# Power.net
KiCad netlist of a schematic drawn in Altium Designer
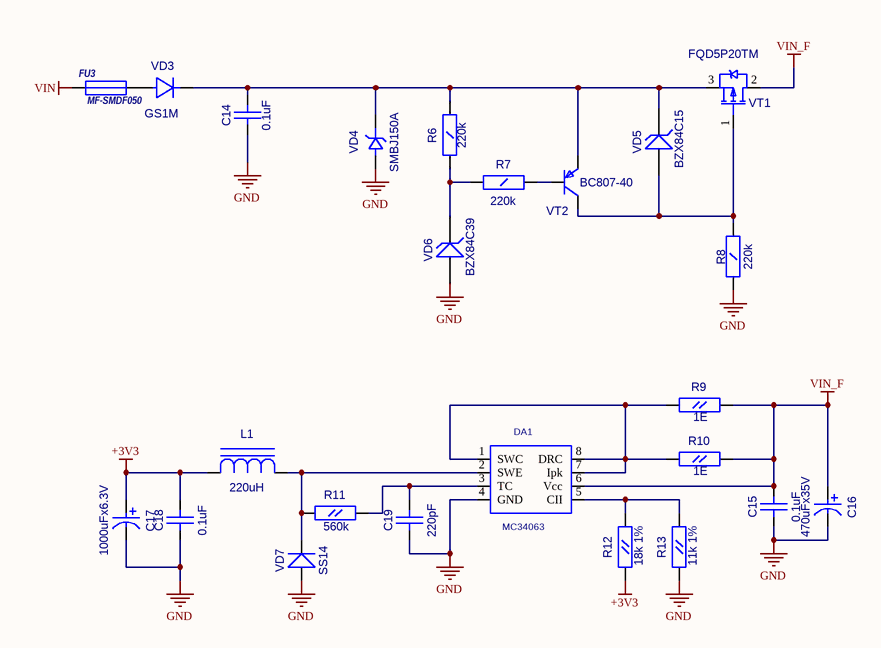
[diagram p0: Power.SchDoc]

(export (version "E")
  (design (tool "Eeschema 10.0.6"))
  (components
    (comp (ref "C14")
      (value "0.1uF")
      (footprint "CC1206")
      (description "CC1206")
      (libsource (lib "gprs_modem_2") (part "CC1206"))
    )
    (comp (ref "C15")
      (value "0.1uF")
      (footprint "CC0603")
      (description "CC0603")
      (libsource (lib "gprs_modem_2") (part "CC0603"))
    )
    (comp (ref "C16")
      (value "470uFx35V")
      (footprint "CC16X10_CAP0.5(1)(Primary)")
      (description "CAP0.5(1)")
      (libsource (lib "gprs_modem_2") (part "CAP0.5(1)"))
    )
    (comp (ref "C17")
      (value "1000uFx6.3V")
      (footprint "CC8X3.5")
      (description "CAP0.35")
      (libsource (lib "gprs_modem_2") (part "CAP0.35"))
    )
    (comp (ref "C18")
      (value "0.1uF")
      (footprint "CC0603")
      (description "CC0603")
      (libsource (lib "gprs_modem_2") (part "CC0603"))
    )
    (comp (ref "C19")
      (value "220pF")
      (footprint "CC0603")
      (description "CC0603")
      (libsource (lib "gprs_modem_2") (part "CC0603"))
    )
    (comp (ref "DA1") (value "MC34063") (footprint "SO-8") (libsource (lib "Schetchik") (part "MC34063")))
    (comp (ref "FU3")
      (value "MF-SMDF050")
      (footprint "MF-SMDF")
      (description "MF-SMDF")
      (libsource (lib "gprs_modem_2") (part "MF-SMDF"))
    )
    (comp (ref "L1")
      (value "220uH")
      (footprint "SDR0805")
      (description "SDR0805")
      (libsource (lib "gprs_modem_2") (part "SDR0805"))
    )
    (comp (ref "R6")
      (value "220k")
      (footprint "RC1206")
      (description "RC1206")
      (libsource (lib "gprs_modem_2") (part "RC1206"))
    )
    (comp (ref "R7")
      (value "220k")
      (footprint "RC1206")
      (description "RC1206")
      (libsource (lib "gprs_modem_2") (part "RC1206"))
    )
    (comp (ref "R8")
      (value "220k")
      (footprint "RC1206")
      (description "RC1206")
      (libsource (lib "gprs_modem_2") (part "RC1206"))
    )
    (comp (ref "R9")
      (value "1E")
      (footprint "RC0805")
      (description "RC0805")
      (libsource (lib "gprs_modem_2") (part "RC0805"))
    )
    (comp (ref "R10")
      (value "1E")
      (footprint "RC0805")
      (description "RC0805")
      (libsource (lib "gprs_modem_2") (part "RC0805"))
    )
    (comp (ref "R11")
      (value "560k")
      (footprint "RC0603")
      (description "RC0603")
      (libsource (lib "gprs_modem_2") (part "RC0603"))
    )
    (comp (ref "R12")
      (value "18k 1%")
      (footprint "RC0603")
      (description "RC0603")
      (libsource (lib "gprs_modem_2") (part "RC0603"))
    )
    (comp (ref "R13")
      (value "11k 1%")
      (footprint "RC0603")
      (description "RC0603")
      (libsource (lib "gprs_modem_2") (part "RC0603"))
    )
    (comp (ref "VD3") (value "GS1M") (footprint "SMA") (libsource (lib "gprs_modem") (part "GS1M")))
    (comp (ref "VD4")
      (value "SMBJ150A")
      (footprint "SMB")
      (description "SMBJ")
      (libsource (lib "gprs_modem_2") (part "SMBJ"))
    )
    (comp (ref "VD5")
      (value "BZX84C15")
      (footprint "SOT-23(123)")
      (description "Zener Voltage Regulator Diode")
      (libsource (lib "gprs_modem_2") (part "BZX84"))
    )
    (comp (ref "VD6")
      (value "BZX84C39")
      (footprint "SOT-23(123)")
      (description "Zener Voltage Regulator Diode")
      (libsource (lib "gprs_modem_2") (part "BZX84"))
    )
    (comp (ref "VD7")
      (value "SS14")
      (footprint "SMA")
      (description "Schottky Rectifier")
      (libsource (lib "gprs_modem_2") (part "SS14"))
    )
    (comp (ref "VT1")
      (value "FQD5P20TM")
      (footprint "D-PAK(TO-252AA)")
      (description "HEXFET Power MOSFET")
      (libsource (lib "gprs_modem_2") (part "IRFR9220"))
    )
    (comp (ref "VT2")
      (value "BC807-40")
      (footprint "SOT-23(123)")
      (description "BC857B")
      (libsource (lib "gprs_modem") (part "BC857B"))
    )
  )
  (nets
    (net (code "1") (name "+3V3") (class "Default")
      (node (ref "C17") (pin "1") (pintype "passive"))
      (node (ref "C18") (pin "2") (pinfunction "B_2") (pintype "passive"))
      (node (ref "L1") (pin "1") (pinfunction "C_1") (pintype "passive"))
      (node (ref "R12") (pin "1") (pinfunction "A_1") (pintype "passive"))
    )
    (net (code "2") (name "GND") (class "Default")
      (node (ref "C14") (pin "1") (pinfunction "A_1") (pintype "passive"))
      (node (ref "C15") (pin "1") (pinfunction "A_1") (pintype "passive"))
      (node (ref "C16") (pin "1") (pintype "passive"))
      (node (ref "C17") (pin "2") (pintype "passive"))
      (node (ref "C18") (pin "1") (pinfunction "A_1") (pintype "passive"))
      (node (ref "C19") (pin "1") (pinfunction "A_1") (pintype "passive"))
      (node (ref "DA1") (pin "4") (pinfunction "GND_4") (pintype "passive"))
      (node (ref "R13") (pin "1") (pinfunction "A_1") (pintype "passive"))
      (node (ref "R8") (pin "2") (pinfunction "B_2") (pintype "passive"))
      (node (ref "VD4") (pin "1") (pinfunction "A_1") (pintype "passive"))
      (node (ref "VD6") (pin "1") (pinfunction "A_1") (pintype "passive"))
      (node (ref "VD7") (pin "1") (pinfunction "A_1") (pintype "passive"))
    )
    (net (code "3") (name "Net-(C14-B)") (class "Default")
      (node (ref "C14") (pin "2") (pinfunction "B_2") (pintype "passive"))
      (node (ref "R6") (pin "2") (pinfunction "B_2") (pintype "passive"))
      (node (ref "VD3") (pin "2") (pinfunction "K_2") (pintype "passive"))
      (node (ref "VD4") (pin "2") (pinfunction "K_2") (pintype "passive"))
      (node (ref "VD5") (pin "3") (pinfunction "K_3") (pintype "passive"))
      (node (ref "VT1") (pin "3") (pinfunction "S_3") (pintype "passive"))
      (node (ref "VT2") (pin "2") (pinfunction "E_2") (pintype "passive"))
    )
    (net (code "4") (name "Net-(C19-B)") (class "Default")
      (node (ref "C19") (pin "2") (pinfunction "B_2") (pintype "passive"))
      (node (ref "DA1") (pin "3") (pinfunction "TC_3") (pintype "passive"))
      (node (ref "R11") (pin "2") (pinfunction "B_2") (pintype "passive"))
    )
    (net (code "5") (name "Net-(DA1-CII)") (class "Default")
      (node (ref "DA1") (pin "5") (pinfunction "CII_5") (pintype "passive"))
      (node (ref "R12") (pin "2") (pinfunction "B_2") (pintype "passive"))
      (node (ref "R13") (pin "2") (pinfunction "B_2") (pintype "passive"))
    )
    (net (code "6") (name "Net-(DA1-DRC)") (class "Default")
      (node (ref "DA1") (pin "1") (pinfunction "SWC_1") (pintype "passive"))
      (node (ref "DA1") (pin "7") (pinfunction "Ipk_7") (pintype "passive"))
      (node (ref "DA1") (pin "8") (pinfunction "DRC_8") (pintype "passive"))
      (node (ref "R10") (pin "1") (pinfunction "A_1") (pintype "passive"))
      (node (ref "R9") (pin "1") (pinfunction "A_1") (pintype "passive"))
    )
    (net (code "7") (name "Net-(DA1-SWE)") (class "Default")
      (node (ref "DA1") (pin "2") (pinfunction "SWE_2") (pintype "passive"))
      (node (ref "L1") (pin "2") (pinfunction "A_2") (pintype "passive"))
      (node (ref "R11") (pin "1") (pinfunction "A_1") (pintype "passive"))
      (node (ref "VD7") (pin "2") (pinfunction "K_2") (pintype "passive"))
    )
    (net (code "8") (name "Net-(R6-A)") (class "Default")
      (node (ref "R6") (pin "1") (pinfunction "A_1") (pintype "passive"))
      (node (ref "R7") (pin "1") (pinfunction "A_1") (pintype "passive"))
      (node (ref "VD6") (pin "3") (pinfunction "K_3") (pintype "passive"))
    )
    (net (code "9") (name "Net-(R7-B)") (class "Default")
      (node (ref "R7") (pin "2") (pinfunction "B_2") (pintype "passive"))
      (node (ref "VT2") (pin "1") (pinfunction "B_1") (pintype "passive"))
    )
    (net (code "10") (name "Net-(R8-A)") (class "Default")
      (node (ref "R8") (pin "1") (pinfunction "A_1") (pintype "passive"))
      (node (ref "VD5") (pin "1") (pinfunction "A_1") (pintype "passive"))
      (node (ref "VT1") (pin "1") (pinfunction "G_1") (pintype "passive"))
      (node (ref "VT2") (pin "3") (pinfunction "C_3") (pintype "passive"))
    )
    (net (code "11") (name "Net-(VD3-A)") (class "Default")
      (node (ref "FU3") (pin "2") (pintype "passive"))
      (node (ref "VD3") (pin "1") (pinfunction "A_1") (pintype "passive"))
    )
    (net (code "12") (name "VIN") (class "Default") (node (ref "FU3") (pin "1") (pintype "passive")))
    (net (code "13") (name "VIN_F") (class "Default")
      (node (ref "C15") (pin "2") (pinfunction "B_2") (pintype "passive"))
      (node (ref "C16") (pin "2") (pintype "passive"))
      (node (ref "DA1") (pin "6") (pinfunction "Vcc_6") (pintype "passive"))
      (node (ref "R10") (pin "2") (pinfunction "B_2") (pintype "passive"))
      (node (ref "R9") (pin "2") (pinfunction "B_2") (pintype "passive"))
      (node (ref "VT1") (pin "2") (pinfunction "D_2") (pintype "passive"))
    )
  )
)
